# fsr_electrode.net
KiCad netlist of a schematic drawn in EAGLE
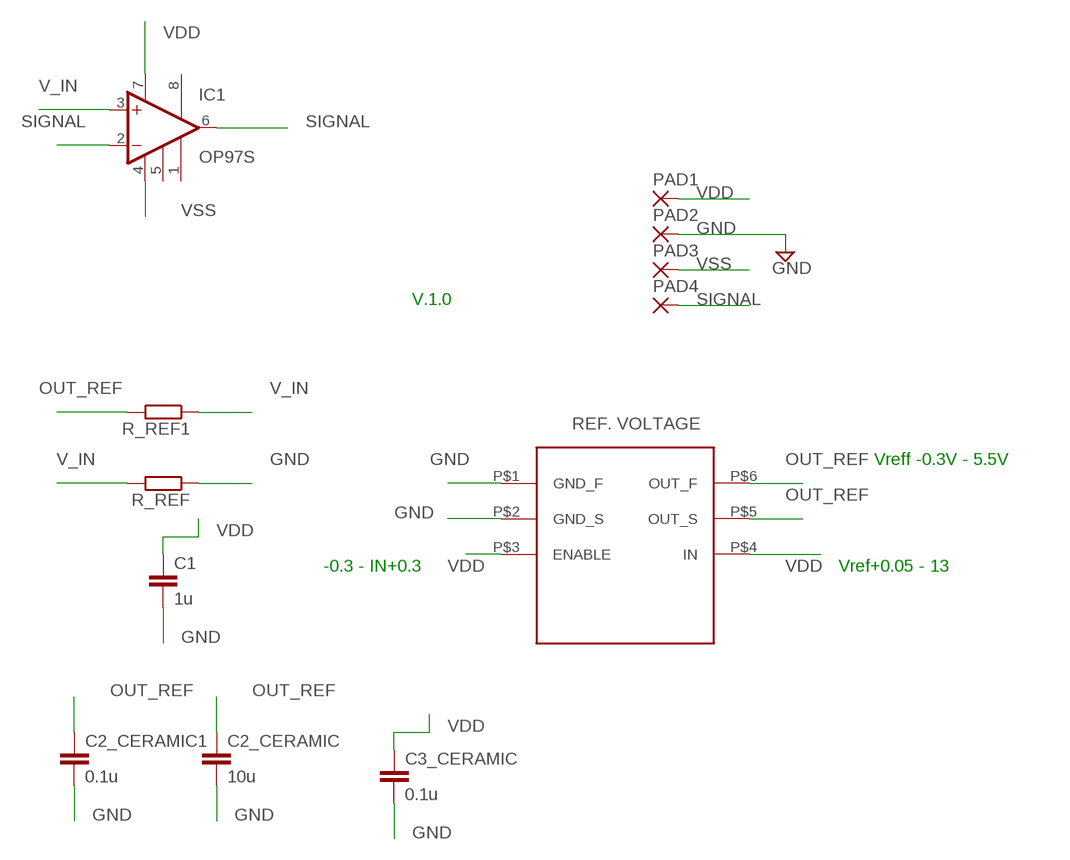
[diagram p0: schematic, sheet 1]

(export (version "E")
  (design (tool "Eeschema 10.0.6"))
  (components
    (comp (ref "C1")
      (value "1u")
      (footprint "eagle-import:C0805")
      (libsource (lib "eagle-import") (part "C-EUC0805"))
    )
    (comp (ref "C2_CERAMIC")
      (value "10u")
      (footprint "eagle-import:C0805")
      (libsource (lib "eagle-import") (part "C-EUC0805"))
    )
    (comp (ref "C2_CERAMIC1")
      (value "0.1u")
      (footprint "eagle-import:C0805")
      (libsource (lib "eagle-import") (part "C-EUC0805"))
    )
    (comp (ref "C3_CERAMIC")
      (value "0.1u")
      (footprint "eagle-import:C0805")
      (libsource (lib "eagle-import") (part "C-EUC0805"))
    )
    (comp (ref "IC1")
      (value "OP97S")
      (footprint "eagle-import:SO08")
      (libsource (lib "eagle-import") (part "OP97S"))
    )
    (comp (ref "PAD1")
      (value "SMD5")
      (footprint "eagle-import:SMD2,54-5,08")
      (libsource (lib "eagle-import") (part "SMD5"))
    )
    (comp (ref "PAD2")
      (value "SMD5")
      (footprint "eagle-import:SMD2,54-5,08")
      (libsource (lib "eagle-import") (part "SMD5"))
    )
    (comp (ref "PAD3")
      (value "SMD5")
      (footprint "eagle-import:SMD2,54-5,08")
      (libsource (lib "eagle-import") (part "SMD5"))
    )
    (comp (ref "PAD4")
      (value "SMD5")
      (footprint "eagle-import:SMD2,54-5,08")
      (libsource (lib "eagle-import") (part "SMD5"))
    )
    (comp (ref "REF3450")
      (value "REF3450IDBVR")
      (footprint "eagle-import:UZUN")
      (libsource (lib "eagle-import") (part "REF3450IDBVR"))
    )
    (comp (ref "R_REF")
      (value "10k")
      (footprint "eagle-import:M0805")
      (libsource (lib "eagle-import") (part "R-EU_M0805"))
    )
    (comp (ref "R_REF1")
      (value "10k")
      (footprint "eagle-import:M0805")
      (libsource (lib "eagle-import") (part "R-EU_M0805"))
    )
  )
  (nets
    (net (code "1") (name "/OUT_REF") (class "Default")
      (node (ref "C2_CERAMIC") (pin "1") (pinfunction "1_1") (pintype "passive"))
      (node (ref "C2_CERAMIC1") (pin "1") (pinfunction "1_1") (pintype "passive"))
      (node (ref "REF3450") (pin "P$5") (pinfunction "OUT_S_P$5") (pintype "bidirectional"))
      (node (ref "REF3450") (pin "P$6") (pinfunction "OUT_F_P$6") (pintype "bidirectional"))
      (node (ref "R_REF1") (pin "2") (pinfunction "2_2") (pintype "passive"))
    )
    (net (code "2") (name "/SIGNAL") (class "Default")
      (node (ref "IC1") (pin "2") (pinfunction "-IN_2") (pintype "input"))
      (node (ref "IC1") (pin "6") (pinfunction "OUT_6") (pintype "output"))
      (node (ref "PAD4") (pin "1") (pinfunction "P_1") (pintype "passive"))
    )
    (net (code "3") (name "/VDD") (class "Default")
      (node (ref "C1") (pin "1") (pinfunction "1_1") (pintype "passive"))
      (node (ref "C3_CERAMIC") (pin "1") (pinfunction "1_1") (pintype "passive"))
      (node (ref "IC1") (pin "7") (pinfunction "V+_7") (pintype "power_in"))
      (node (ref "PAD1") (pin "1") (pinfunction "P_1") (pintype "passive"))
      (node (ref "REF3450") (pin "P$3") (pinfunction "ENABLE_P$3") (pintype "bidirectional"))
      (node (ref "REF3450") (pin "P$4") (pinfunction "IN_P$4") (pintype "bidirectional"))
    )
    (net (code "4") (name "/VSS") (class "Default")
      (node (ref "IC1") (pin "4") (pinfunction "V-_4") (pintype "power_in"))
      (node (ref "PAD3") (pin "1") (pinfunction "P_1") (pintype "passive"))
    )
    (net (code "5") (name "/V_IN") (class "Default")
      (node (ref "IC1") (pin "3") (pinfunction "+IN_3") (pintype "input"))
      (node (ref "R_REF") (pin "2") (pinfunction "2_2") (pintype "passive"))
      (node (ref "R_REF1") (pin "1") (pinfunction "1_1") (pintype "passive"))
    )
    (net (code "6") (name "GND") (class "Default")
      (node (ref "C1") (pin "2") (pinfunction "2_2") (pintype "passive"))
      (node (ref "C2_CERAMIC") (pin "2") (pinfunction "2_2") (pintype "passive"))
      (node (ref "C2_CERAMIC1") (pin "2") (pinfunction "2_2") (pintype "passive"))
      (node (ref "C3_CERAMIC") (pin "2") (pinfunction "2_2") (pintype "passive"))
      (node (ref "PAD2") (pin "1") (pinfunction "P_1") (pintype "passive"))
      (node (ref "REF3450") (pin "P$1") (pinfunction "GND_F_P$1") (pintype "bidirectional"))
      (node (ref "REF3450") (pin "P$2") (pinfunction "GND_S_P$2") (pintype "bidirectional"))
      (node (ref "R_REF") (pin "1") (pinfunction "1_1") (pintype "passive"))
    )
    (net (code "7") (name "unconnected-(IC1-BAL1-Pad1)") (class "Default")
      (node (ref "IC1") (pin "1") (pinfunction "BAL1_1") (pintype "passive"))
    )
    (net (code "8") (name "unconnected-(IC1-BAL2-Pad8)") (class "Default")
      (node (ref "IC1") (pin "8") (pinfunction "BAL2_8") (pintype "passive"))
    )
    (net (code "9") (name "unconnected-(IC1-COMP-Pad5)") (class "Default")
      (node (ref "IC1") (pin "5") (pinfunction "COMP_5") (pintype "passive"))
    )
  )
)
